# Core_Power.net
KiCad netlist of a schematic drawn in Altium Designer
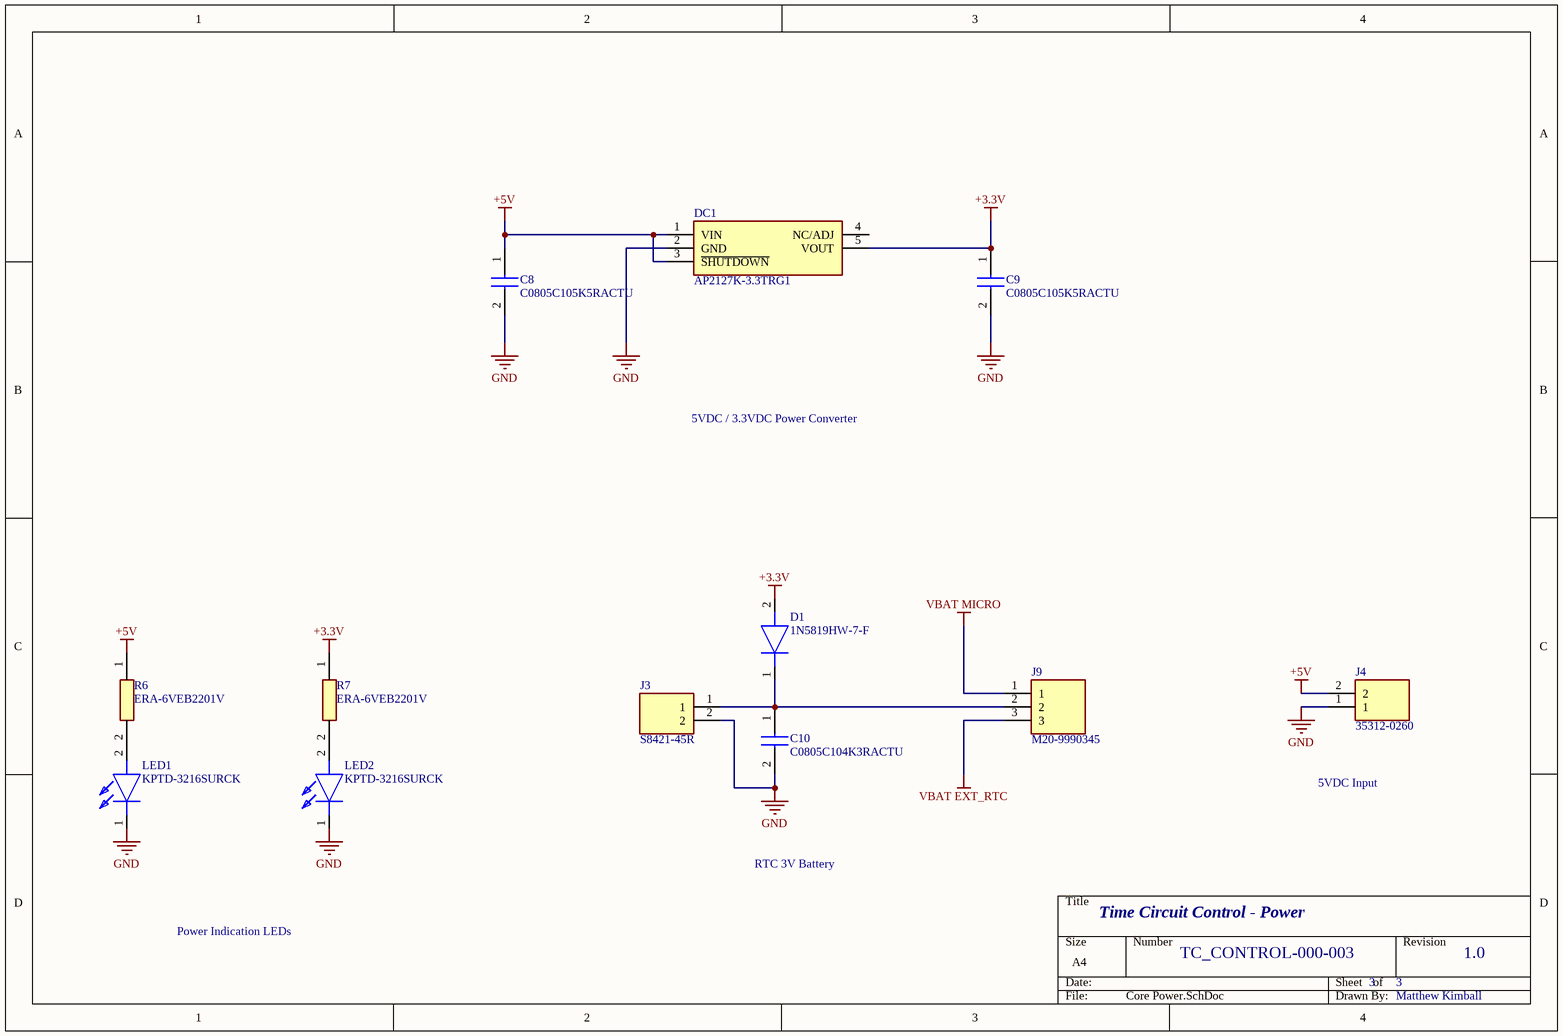
[diagram p0: Core Power.SchDoc]

(export (version "E")
  (design (tool "Eeschema 10.0.6"))
  (components
    (comp (ref "C8")
      (value "C0805C105K5RACTU")
      (footprint "SamacSys:CAPC2012X140N")
      (description "Capacitor")
      (fields (field (name "MOUSER PART NUMBER") "80-C0805C105K5R"))
      (libsource (lib "SamacSys") (part "C0805C105K5RACTU"))
    )
    (comp (ref "C9")
      (value "C0805C105K5RACTU")
      (footprint "SamacSys:CAPC2012X140N")
      (description "Capacitor")
      (fields (field (name "MOUSER PART NUMBER") "80-C0805C105K5R"))
      (libsource (lib "SamacSys") (part "C0805C105K5RACTU"))
    )
    (comp (ref "C10")
      (value "C0805C104K3RACTU")
      (footprint "SamacSys:CAPC2012X88N")
      (description "Capacitor")
      (fields (field (name "MOUSER PART NUMBER") "80-C0805C104K3R"))
      (libsource (lib "SamacSys") (part "C0805C104K3RACTU"))
    )
    (comp (ref "D1")
      (value "1N5819HW-7-F")
      (footprint "SamacSys:SOD3716X125N")
      (description "Diode")
      (libsource (lib "*") (part "1N5819HW-7-F"))
    )
    (comp (ref "DC1")
      (value "AP2127K-3.3TRG1")
      (footprint "SamacSys:SOT95P282X145-5N")
      (description "Integrated Circuit")
      (fields (field (name "MOUSER PART NUMBER") "621-AP2127K-3.3TRG1"))
      (libsource (lib "SamacSys") (part "AP2127K-3.3TRG1"))
    )
    (comp (ref "J3")
      (value "S8421-45R")
      (footprint "SamacSys:S8421-45R_1")
      (description "Connector")
      (fields (field (name "MOUSER PART NUMBER") "855-S8421-45R"))
      (libsource (lib "SamacSys") (part "S8421-45R"))
    )
    (comp (ref "J4")
      (value "35312-0260")
      (footprint "SamacSys:SHDR2W64P0X250_1X2_746X650X700P")
      (description "Connector")
      (fields (field (name "MOUSER PART NUMBER") "538-35312-0260"))
      (libsource (lib "SamacSys") (part "35312-0260"))
    )
    (comp (ref "J9")
      (value "M20-9990345")
      (footprint "SamacSys:HDRV3W64P0X254_1X3_762X254X864P")
      (description "2.54 pitch SIL vertical PC tail pin header")
      (fields (field (name "MOUSER PART NUMBER") "855-M20-9990345"))
      (libsource (lib "SamacSys") (part "M20-9990345"))
    )
    (comp (ref "LED1")
      (value "KPTD-3216SURCK")
      (footprint "SamacSys:KPTD3216SURCK")
      (description "LED")
      (libsource (lib "SamacSys") (part "KPTD-3216SURCK"))
    )
    (comp (ref "LED2")
      (value "KPTD-3216SURCK")
      (footprint "SamacSys:KPTD3216SURCK")
      (description "LED")
      (libsource (lib "SamacSys") (part "KPTD-3216SURCK"))
    )
    (comp (ref "R6")
      (value "ERA-6VEB2201V")
      (footprint "SamacSys:RESC2012X65N")
      (description "Resistor")
      (fields (field (name "MOUSER PART NUMBER") "667-ERA-6VEB2201V"))
      (libsource (lib "SamacSys") (part "ERA-6VEB2201V"))
    )
    (comp (ref "R7")
      (value "ERA-6VEB2201V")
      (footprint "SamacSys:RESC2012X65N")
      (description "Resistor")
      (fields (field (name "MOUSER PART NUMBER") "667-ERA-6VEB2201V"))
      (libsource (lib "SamacSys") (part "ERA-6VEB2201V"))
    )
  )
  (nets
    (net (code "1") (name "+3.3V") (class "Default")
      (node (ref "C9") (pin "1") (pinfunction "1_1") (pintype "passive"))
      (node (ref "D1") (pin "2") (pinfunction "A_2") (pintype "passive"))
      (node (ref "DC1") (pin "5") (pinfunction "VOUT_5") (pintype "passive"))
      (node (ref "R7") (pin "1") (pinfunction "1_1") (pintype "passive"))
    )
    (net (code "2") (name "+5V") (class "Default")
      (node (ref "C8") (pin "1") (pinfunction "1_1") (pintype "passive"))
      (node (ref "DC1") (pin "1") (pinfunction "VIN_1") (pintype "passive"))
      (node (ref "DC1") (pin "3") (pinfunction "~{SHUTDOWN}_3") (pintype "passive"))
      (node (ref "J4") (pin "2") (pinfunction "2_2") (pintype "passive"))
      (node (ref "R6") (pin "1") (pinfunction "1_1") (pintype "passive"))
    )
    (net (code "3") (name "GND") (class "Default")
      (node (ref "C10") (pin "2") (pinfunction "2_2") (pintype "passive"))
      (node (ref "C8") (pin "2") (pinfunction "2_2") (pintype "passive"))
      (node (ref "C9") (pin "2") (pinfunction "2_2") (pintype "passive"))
      (node (ref "DC1") (pin "2") (pinfunction "GND_2") (pintype "passive"))
      (node (ref "J3") (pin "2") (pinfunction "2_2") (pintype "passive"))
      (node (ref "J4") (pin "1") (pinfunction "1_1") (pintype "passive"))
      (node (ref "LED1") (pin "1") (pinfunction "K_1") (pintype "passive"))
      (node (ref "LED2") (pin "1") (pinfunction "K_1") (pintype "passive"))
    )
    (net (code "4") (name "Net-(D1-K)") (class "Default")
      (node (ref "C10") (pin "1") (pinfunction "1_1") (pintype "passive"))
      (node (ref "D1") (pin "1") (pinfunction "K_1") (pintype "passive"))
      (node (ref "J3") (pin "1") (pinfunction "1_1") (pintype "passive"))
      (node (ref "J9") (pin "2") (pinfunction "2_2") (pintype "passive"))
    )
    (net (code "5") (name "Net-(LED1-A)") (class "Default")
      (node (ref "LED1") (pin "2") (pinfunction "A_2") (pintype "passive"))
      (node (ref "R6") (pin "2") (pinfunction "2_2") (pintype "passive"))
    )
    (net (code "6") (name "Net-(LED2-A)") (class "Default")
      (node (ref "LED2") (pin "2") (pinfunction "A_2") (pintype "passive"))
      (node (ref "R7") (pin "2") (pinfunction "2_2") (pintype "passive"))
    )
    (net (code "7") (name "VBAT EXT_RTC") (class "Default")
      (node (ref "J9") (pin "3") (pinfunction "3_3") (pintype "passive"))
    )
    (net (code "8") (name "VBAT MICRO") (class "Default")
      (node (ref "J9") (pin "1") (pinfunction "1_1") (pintype "passive"))
    )
    (net (code "9") (name "unconnected-(DC1-NC{slash}ADJ-Pad4)") (class "Default")
      (node (ref "DC1") (pin "4") (pinfunction "NC/ADJ_4") (pintype "passive"))
    )
  )
)
